# audio.net
KiCad netlist of a schematic drawn in EAGLE
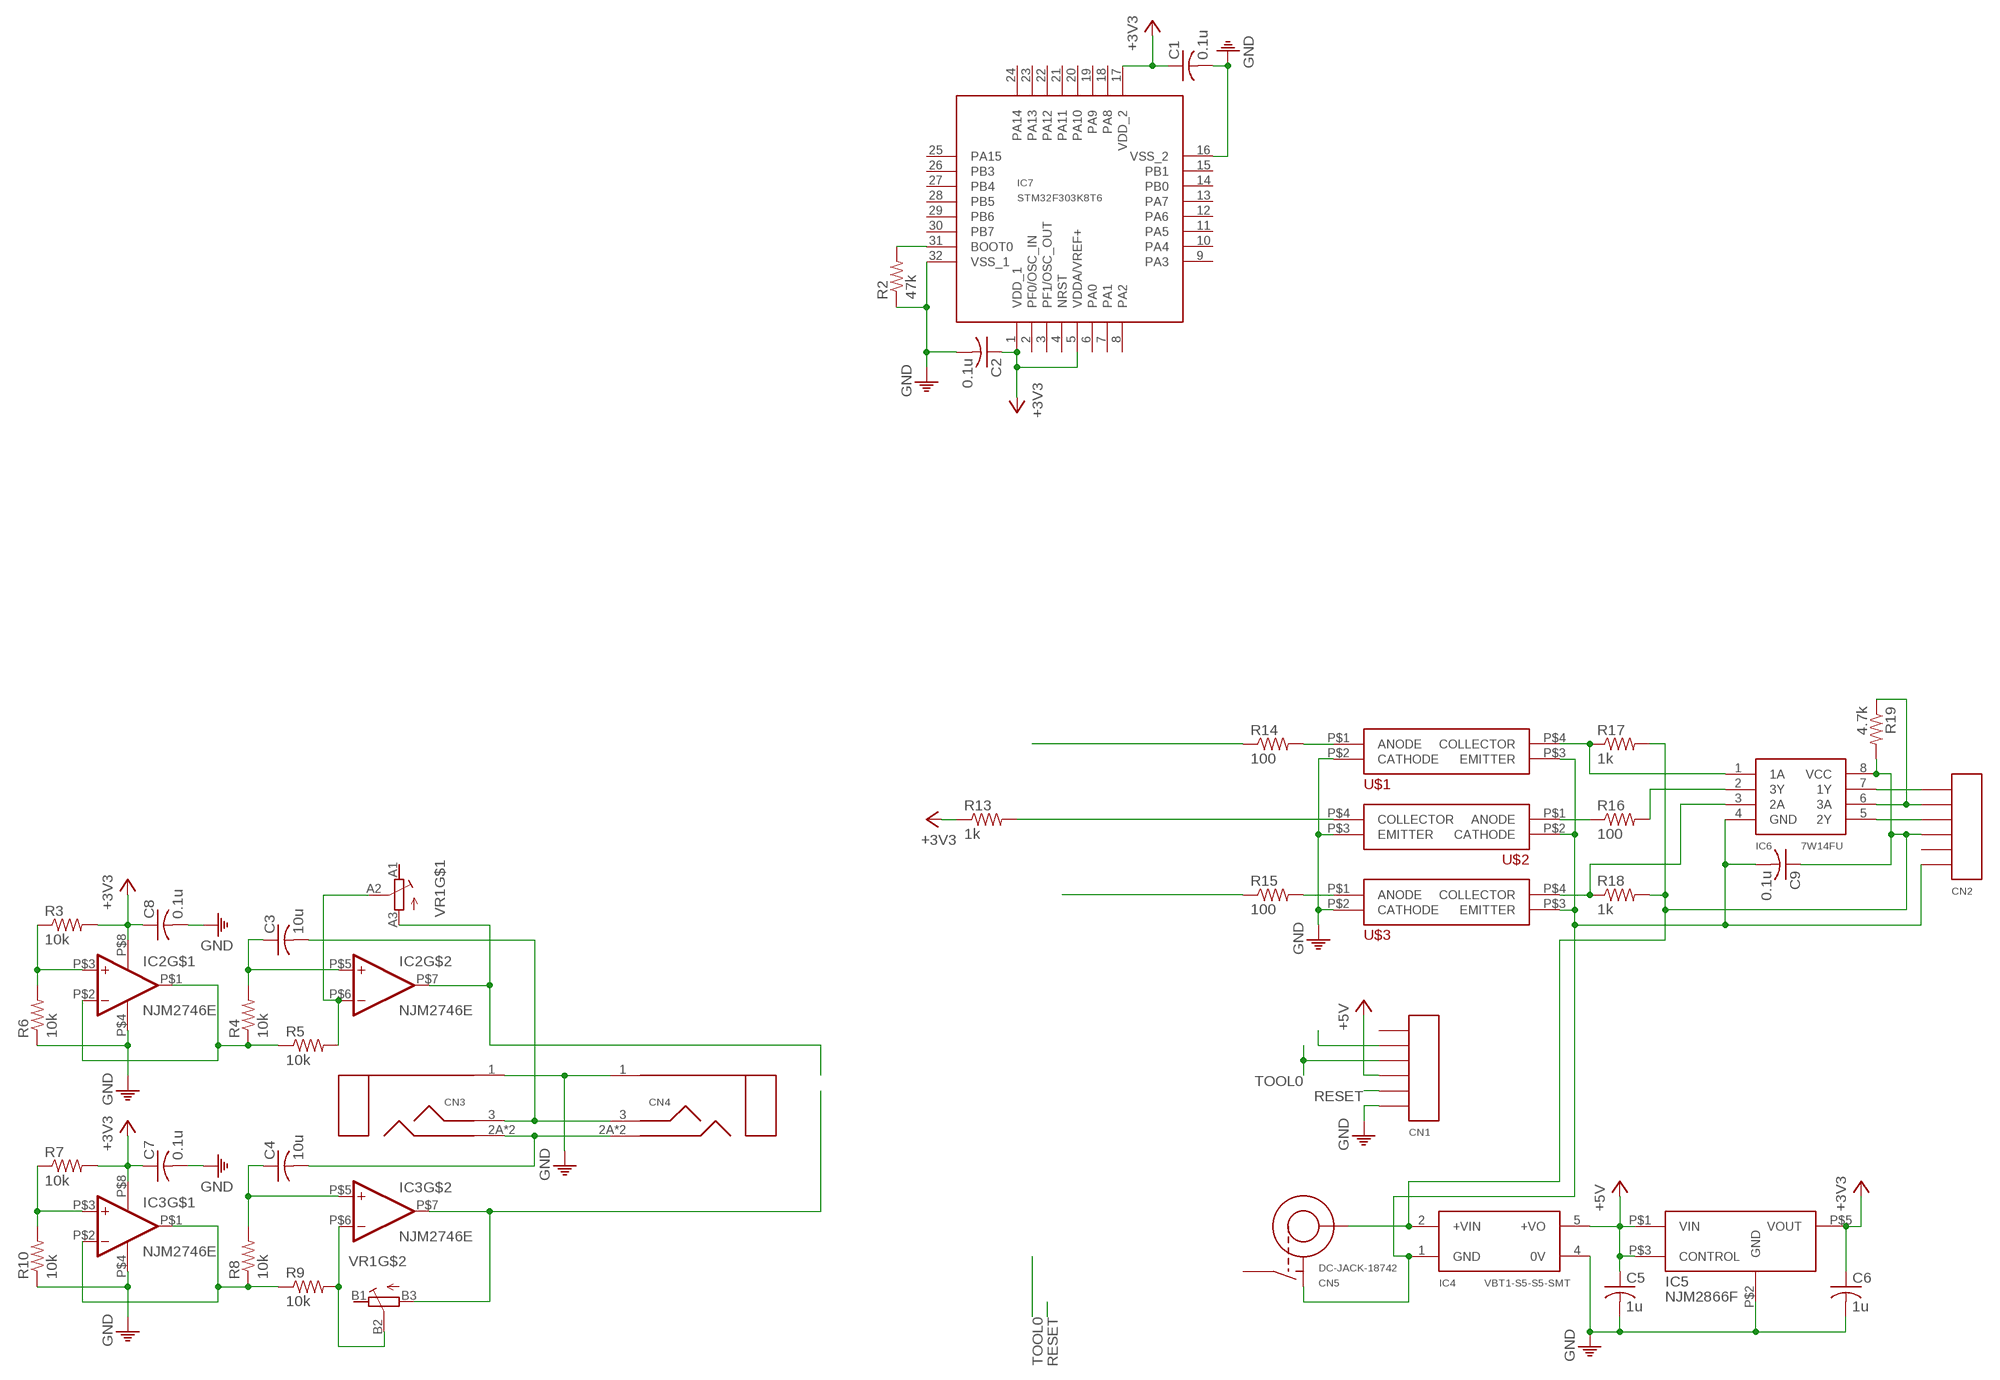
[diagram p0: schematic, sheet 1]

(export (version "E")
  (design (tool "Eeschema 10.0.6"))
  (components
    (comp (ref "C1")
      (value "0.1u")
      (footprint "eagle-import:C2012")
      (libsource (lib "eagle-import") (part "C2012"))
    )
    (comp (ref "C2")
      (value "0.1u")
      (footprint "eagle-import:C2012")
      (libsource (lib "eagle-import") (part "C2012"))
    )
    (comp (ref "C3")
      (value "10u")
      (footprint "eagle-import:C2012")
      (libsource (lib "eagle-import") (part "C2012"))
    )
    (comp (ref "C4")
      (value "10u")
      (footprint "eagle-import:C2012")
      (libsource (lib "eagle-import") (part "C2012"))
    )
    (comp (ref "C5")
      (value "1u")
      (footprint "eagle-import:C2012")
      (libsource (lib "eagle-import") (part "C2012"))
    )
    (comp (ref "C6")
      (value "1u")
      (footprint "eagle-import:C2012")
      (libsource (lib "eagle-import") (part "C2012"))
    )
    (comp (ref "C7")
      (value "0.1u")
      (footprint "eagle-import:C2012")
      (libsource (lib "eagle-import") (part "C2012"))
    )
    (comp (ref "C8")
      (value "0.1u")
      (footprint "eagle-import:C2012")
      (libsource (lib "eagle-import") (part "C2012"))
    )
    (comp (ref "C9")
      (value "0.1u")
      (footprint "eagle-import:C2012")
      (libsource (lib "eagle-import") (part "C2012"))
    )
    (comp (ref "CN1")
      (value "PH-1X06SG")
      (footprint "eagle-import:PH-1X06SG")
      (libsource (lib "eagle-import") (part "PH-1X06SG"))
    )
    (comp (ref "CN2")
      (value "PH-1X06RG")
      (footprint "eagle-import:PH-1X06RG")
      (libsource (lib "eagle-import") (part "PH-1X06RG"))
    )
    (comp (ref "CN3")
      (value "STEREO-3.5-MJ8435")
      (footprint "eagle-import:MJ8435")
      (libsource (lib "eagle-import") (part "STEREO-3.5-MJ8435"))
    )
    (comp (ref "CN4")
      (value "STEREO-3.5-MJ8435")
      (footprint "eagle-import:MJ8435")
      (libsource (lib "eagle-import") (part "STEREO-3.5-MJ8435"))
    )
    (comp (ref "CN5")
      (value "DC-JACK-18742")
      (footprint "eagle-import:18742")
      (libsource (lib "eagle-import") (part "DC-JACK-18742"))
    )
    (comp (ref "IC2")
      (value "NJM2746E")
      (footprint "eagle-import:EMP8")
      (libsource (lib "eagle-import") (part "NJM2746E"))
    )
    (comp (ref "IC3")
      (value "NJM2746E")
      (footprint "eagle-import:EMP8")
      (libsource (lib "eagle-import") (part "NJM2746E"))
    )
    (comp (ref "IC4")
      (value "VBT1-S5-S5-SMT")
      (footprint "eagle-import:VBT1-S5-S5-SMT")
      (libsource (lib "eagle-import") (part "VBT1-S5-S5-SMT"))
    )
    (comp (ref "IC5")
      (value "NJM2866F")
      (footprint "eagle-import:SOT-23-5")
      (libsource (lib "eagle-import") (part "NJM2866F"))
    )
    (comp (ref "IC6")
      (value "7W14FU")
      (footprint "eagle-import:SSOP8-P-0.65")
      (libsource (lib "eagle-import") (part "714FUW"))
    )
    (comp (ref "IC7")
      (value "STM32F303K8T6")
      (footprint "eagle-import:P-LQFP32-7X7-0.80")
      (libsource (lib "eagle-import") (part "STM32F303K8T6"))
    )
    (comp (ref "R2")
      (value "47k")
      (footprint "eagle-import:R2012")
      (libsource (lib "eagle-import") (part "R2012"))
    )
    (comp (ref "R3")
      (value "10k")
      (footprint "eagle-import:R2012")
      (libsource (lib "eagle-import") (part "R2012"))
    )
    (comp (ref "R4")
      (value "10k")
      (footprint "eagle-import:R2012")
      (libsource (lib "eagle-import") (part "R2012"))
    )
    (comp (ref "R5")
      (value "10k")
      (footprint "eagle-import:R2012")
      (libsource (lib "eagle-import") (part "R2012"))
    )
    (comp (ref "R6")
      (value "10k")
      (footprint "eagle-import:R2012")
      (libsource (lib "eagle-import") (part "R2012"))
    )
    (comp (ref "R7")
      (value "10k")
      (footprint "eagle-import:R2012")
      (libsource (lib "eagle-import") (part "R2012"))
    )
    (comp (ref "R8")
      (value "10k")
      (footprint "eagle-import:R2012")
      (libsource (lib "eagle-import") (part "R2012"))
    )
    (comp (ref "R9")
      (value "10k")
      (footprint "eagle-import:R2012")
      (libsource (lib "eagle-import") (part "R2012"))
    )
    (comp (ref "R10")
      (value "10k")
      (footprint "eagle-import:R2012")
      (libsource (lib "eagle-import") (part "R2012"))
    )
    (comp (ref "R13")
      (value "1k")
      (footprint "eagle-import:R2012")
      (libsource (lib "eagle-import") (part "R2012"))
    )
    (comp (ref "R14")
      (value "100")
      (footprint "eagle-import:R2012")
      (libsource (lib "eagle-import") (part "R2012"))
    )
    (comp (ref "R15")
      (value "100")
      (footprint "eagle-import:R2012")
      (libsource (lib "eagle-import") (part "R2012"))
    )
    (comp (ref "R16")
      (value "100")
      (footprint "eagle-import:R2012")
      (libsource (lib "eagle-import") (part "R2012"))
    )
    (comp (ref "R17")
      (value "1k")
      (footprint "eagle-import:R2012")
      (libsource (lib "eagle-import") (part "R2012"))
    )
    (comp (ref "R18")
      (value "1k")
      (footprint "eagle-import:R2012")
      (libsource (lib "eagle-import") (part "R2012"))
    )
    (comp (ref "R19")
      (value "4.7k")
      (footprint "eagle-import:R2012")
      (libsource (lib "eagle-import") (part "R2012"))
    )
    (comp (ref "U$1")
      (value "TLP291")
      (footprint "eagle-import:11-3C1")
      (libsource (lib "eagle-import") (part "TLP291"))
    )
    (comp (ref "U$2")
      (value "TLP291")
      (footprint "eagle-import:11-3C1")
      (libsource (lib "eagle-import") (part "TLP291"))
    )
    (comp (ref "U$3")
      (value "TLP291")
      (footprint "eagle-import:11-3C1")
      (libsource (lib "eagle-import") (part "TLP291"))
    )
    (comp (ref "VR1")
      (value "R-TRIM-RK0971220")
      (footprint "eagle-import:RK0971220-F15-C0-A104")
      (libsource (lib "eagle-import") (part "R-TRIM-RK0971220"))
    )
  )
  (nets
    (net (code "1") (name "+3V3") (class "Default")
      (node (ref "C1") (pin "1") (pinfunction "1_1") (pintype "passive"))
      (node (ref "C2") (pin "1") (pinfunction "1_1") (pintype "passive"))
      (node (ref "C6") (pin "1") (pinfunction "1_1") (pintype "passive"))
      (node (ref "C7") (pin "1") (pinfunction "1_1") (pintype "passive"))
      (node (ref "C8") (pin "1") (pinfunction "1_1") (pintype "passive"))
      (node (ref "IC2") (pin "P$8") (pinfunction "V+_P$8") (pintype "power_in"))
      (node (ref "IC3") (pin "P$8") (pinfunction "V+_P$8") (pintype "power_in"))
      (node (ref "IC5") (pin "P$5") (pinfunction "VOUT_P$5") (pintype "power_in"))
      (node (ref "IC7") (pin "1") (pinfunction "VDD_1_1") (pintype "power_in"))
      (node (ref "IC7") (pin "17") (pinfunction "VDD_2_17") (pintype "power_in"))
      (node (ref "IC7") (pin "5") (pinfunction "VDDA/VREF+_5") (pintype "power_in"))
      (node (ref "R13") (pin "1") (pinfunction "1_1") (pintype "passive"))
      (node (ref "R3") (pin "2") (pinfunction "2_2") (pintype "passive"))
      (node (ref "R7") (pin "2") (pinfunction "2_2") (pintype "passive"))
    )
    (net (code "2") (name "+5V") (class "Default")
      (node (ref "C5") (pin "1") (pinfunction "1_1") (pintype "passive"))
      (node (ref "CN1") (pin "P$4") (pinfunction "P$4_P$4") (pintype "bidirectional"))
      (node (ref "IC4") (pin "5") (pinfunction "+VO_5") (pintype "power_in"))
      (node (ref "IC5") (pin "P$1") (pinfunction "VIN_P$1") (pintype "input"))
      (node (ref "IC5") (pin "P$3") (pinfunction "CONTROL_P$3") (pintype "input"))
    )
    (net (code "3") (name "/RESET") (class "Default")
      (node (ref "CN1") (pin "P$5") (pinfunction "P$5_P$5") (pintype "bidirectional"))
    )
    (net (code "4") (name "/TOOL0") (class "Default")
      (node (ref "CN1") (pin "P$3") (pinfunction "P$3_P$3") (pintype "bidirectional"))
    )
    (net (code "5") (name "GND") (class "Default")
      (node (ref "C1") (pin "2") (pinfunction "2_2") (pintype "passive"))
      (node (ref "C2") (pin "2") (pinfunction "2_2") (pintype "passive"))
      (node (ref "C5") (pin "2") (pinfunction "2_2") (pintype "passive"))
      (node (ref "C6") (pin "2") (pinfunction "2_2") (pintype "passive"))
      (node (ref "C7") (pin "2") (pinfunction "2_2") (pintype "passive"))
      (node (ref "C8") (pin "2") (pinfunction "2_2") (pintype "passive"))
      (node (ref "CN1") (pin "P$6") (pinfunction "P$6_P$6") (pintype "bidirectional"))
      (node (ref "CN3") (pin "1") (pinfunction "SLEEVE_1") (pintype "passive"))
      (node (ref "CN4") (pin "1") (pinfunction "SLEEVE_1") (pintype "passive"))
      (node (ref "IC2") (pin "P$4") (pinfunction "V-_P$4") (pintype "power_in"))
      (node (ref "IC3") (pin "P$4") (pinfunction "V-_P$4") (pintype "power_in"))
      (node (ref "IC4") (pin "4") (pinfunction "0V_4") (pintype "power_in"))
      (node (ref "IC5") (pin "P$2") (pinfunction "GND_P$2") (pintype "power_in"))
      (node (ref "IC7") (pin "16") (pinfunction "VSS_2_16") (pintype "power_in"))
      (node (ref "IC7") (pin "32") (pinfunction "VSS_1_32") (pintype "power_in"))
      (node (ref "R10") (pin "1") (pinfunction "1_1") (pintype "passive"))
      (node (ref "R2") (pin "1") (pinfunction "1_1") (pintype "passive"))
      (node (ref "R6") (pin "1") (pinfunction "1_1") (pintype "passive"))
      (node (ref "U$1") (pin "P$2") (pinfunction "CATHODE_P$2") (pintype "bidirectional"))
      (node (ref "U$2") (pin "P$3") (pinfunction "EMITTER_P$3") (pintype "bidirectional"))
      (node (ref "U$3") (pin "P$2") (pinfunction "CATHODE_P$2") (pintype "bidirectional"))
    )
    (net (code "6") (name "Net-(C4-Pad2)") (class "Default")
      (node (ref "C4") (pin "2") (pinfunction "2_2") (pintype "passive"))
      (node (ref "CN3") (pin "2A") (pinfunction "TIP_2A") (pintype "passive"))
      (node (ref "CN3") (pin "2B") (pinfunction "TIP_2B") (pintype "passive"))
      (node (ref "CN4") (pin "2A") (pinfunction "TIP_2A") (pintype "passive"))
      (node (ref "CN4") (pin "2B") (pinfunction "TIP_2B") (pintype "passive"))
    )
    (net (code "7") (name "Net-(CN3-RING)") (class "Default")
      (node (ref "C3") (pin "2") (pinfunction "2_2") (pintype "passive"))
      (node (ref "CN3") (pin "3") (pinfunction "RING_3") (pintype "passive"))
      (node (ref "CN4") (pin "3") (pinfunction "RING_3") (pintype "passive"))
    )
    (net (code "8") (name "Net-(CN5-CENTER)") (class "Default")
      (node (ref "C9") (pin "1") (pinfunction "1_1") (pintype "passive"))
      (node (ref "CN2") (pin "P$4") (pinfunction "P$4_P$4") (pintype "bidirectional"))
      (node (ref "CN5") (pin "P$1") (pinfunction "CENTER_P$1") (pintype "passive"))
      (node (ref "IC4") (pin "2") (pinfunction "+VIN_2") (pintype "power_in"))
      (node (ref "IC6") (pin "8") (pinfunction "VCC_8") (pintype "power_in"))
      (node (ref "R17") (pin "2") (pinfunction "2_2") (pintype "passive"))
      (node (ref "R18") (pin "2") (pinfunction "2_2") (pintype "passive"))
      (node (ref "R19") (pin "2") (pinfunction "2_2") (pintype "passive"))
    )
    (net (code "9") (name "Net-(CN5-TIP)") (class "Default")
      (node (ref "C9") (pin "2") (pinfunction "2_2") (pintype "passive"))
      (node (ref "CN2") (pin "P$6") (pinfunction "P$6_P$6") (pintype "bidirectional"))
      (node (ref "CN5") (pin "P$2") (pinfunction "TIP_P$2") (pintype "passive"))
      (node (ref "IC4") (pin "1") (pinfunction "GND_1") (pintype "power_in"))
      (node (ref "IC6") (pin "4") (pinfunction "GND_4") (pintype "power_in"))
      (node (ref "U$1") (pin "P$3") (pinfunction "EMITTER_P$3") (pintype "bidirectional"))
      (node (ref "U$2") (pin "P$2") (pinfunction "CATHODE_P$2") (pintype "bidirectional"))
      (node (ref "U$3") (pin "P$3") (pinfunction "EMITTER_P$3") (pintype "bidirectional"))
    )
    (net (code "10") (name "Net-(IC2A-+IN)") (class "Default")
      (node (ref "IC2") (pin "P$3") (pinfunction "+IN_P$3") (pintype "input"))
      (node (ref "R3") (pin "1") (pinfunction "1_1") (pintype "passive"))
      (node (ref "R6") (pin "2") (pinfunction "2_2") (pintype "passive"))
    )
    (net (code "11") (name "Net-(IC2A--IN)") (class "Default")
      (node (ref "IC2") (pin "P$1") (pinfunction "OUT_P$1") (pintype "output"))
      (node (ref "IC2") (pin "P$2") (pinfunction "-IN_P$2") (pintype "input"))
      (node (ref "R4") (pin "1") (pinfunction "1_1") (pintype "passive"))
      (node (ref "R5") (pin "1") (pinfunction "1_1") (pintype "passive"))
    )
    (net (code "12") (name "Net-(IC2B-+IN)") (class "Default")
      (node (ref "C3") (pin "1") (pinfunction "1_1") (pintype "passive"))
      (node (ref "IC2") (pin "P$5") (pinfunction "+IN_P$5") (pintype "input"))
      (node (ref "R4") (pin "2") (pinfunction "2_2") (pintype "passive"))
    )
    (net (code "13") (name "Net-(IC2B--IN)") (class "Default")
      (node (ref "IC2") (pin "P$6") (pinfunction "-IN_P$6") (pintype "input"))
      (node (ref "R5") (pin "2") (pinfunction "2_2") (pintype "passive"))
      (node (ref "VR1") (pin "A2") (pinfunction "S_A2") (pintype "passive"))
    )
    (net (code "14") (name "Net-(IC2B-OUT)") (class "Default")
      (node (ref "IC2") (pin "P$7") (pinfunction "OUT_P$7") (pintype "output"))
      (node (ref "VR1") (pin "A3") (pinfunction "E_A3") (pintype "passive"))
    )
    (net (code "15") (name "Net-(IC3A-+IN)") (class "Default")
      (node (ref "IC3") (pin "P$3") (pinfunction "+IN_P$3") (pintype "input"))
      (node (ref "R10") (pin "2") (pinfunction "2_2") (pintype "passive"))
      (node (ref "R7") (pin "1") (pinfunction "1_1") (pintype "passive"))
    )
    (net (code "16") (name "Net-(IC3A--IN)") (class "Default")
      (node (ref "IC3") (pin "P$1") (pinfunction "OUT_P$1") (pintype "output"))
      (node (ref "IC3") (pin "P$2") (pinfunction "-IN_P$2") (pintype "input"))
      (node (ref "R8") (pin "1") (pinfunction "1_1") (pintype "passive"))
      (node (ref "R9") (pin "1") (pinfunction "1_1") (pintype "passive"))
    )
    (net (code "17") (name "Net-(IC3B-+IN)") (class "Default")
      (node (ref "C4") (pin "1") (pinfunction "1_1") (pintype "passive"))
      (node (ref "IC3") (pin "P$5") (pinfunction "+IN_P$5") (pintype "input"))
      (node (ref "R8") (pin "2") (pinfunction "2_2") (pintype "passive"))
    )
    (net (code "18") (name "Net-(IC3B--IN)") (class "Default")
      (node (ref "IC3") (pin "P$6") (pinfunction "-IN_P$6") (pintype "input"))
      (node (ref "R9") (pin "2") (pinfunction "2_2") (pintype "passive"))
      (node (ref "VR1") (pin "B2") (pinfunction "S_B2") (pintype "passive"))
    )
    (net (code "19") (name "Net-(IC3B-OUT)") (class "Default")
      (node (ref "IC3") (pin "P$7") (pinfunction "OUT_P$7") (pintype "output"))
      (node (ref "VR1") (pin "B3") (pinfunction "E_B3") (pintype "passive"))
    )
    (net (code "20") (name "Net-(IC6-1A)") (class "Default")
      (node (ref "IC6") (pin "1") (pinfunction "1A_1") (pintype "input"))
      (node (ref "R17") (pin "1") (pinfunction "1_1") (pintype "passive"))
      (node (ref "U$1") (pin "P$4") (pinfunction "COLLECTOR_P$4") (pintype "bidirectional"))
    )
    (net (code "21") (name "Net-(IC6-1Y)") (class "Default")
      (node (ref "CN2") (pin "P$1") (pinfunction "P$1_P$1") (pintype "bidirectional"))
      (node (ref "IC6") (pin "7") (pinfunction "1Y_7") (pintype "output"))
    )
    (net (code "22") (name "Net-(IC6-2A)") (class "Default")
      (node (ref "IC6") (pin "3") (pinfunction "2A_3") (pintype "input"))
      (node (ref "R18") (pin "1") (pinfunction "1_1") (pintype "passive"))
      (node (ref "U$3") (pin "P$4") (pinfunction "COLLECTOR_P$4") (pintype "bidirectional"))
    )
    (net (code "23") (name "Net-(IC6-2Y)") (class "Default")
      (node (ref "CN2") (pin "P$3") (pinfunction "P$3_P$3") (pintype "bidirectional"))
      (node (ref "IC6") (pin "5") (pinfunction "2Y_5") (pintype "output"))
    )
    (net (code "24") (name "Net-(IC6-3A)") (class "Default")
      (node (ref "CN2") (pin "P$2") (pinfunction "P$2_P$2") (pintype "bidirectional"))
      (node (ref "IC6") (pin "6") (pinfunction "3A_6") (pintype "input"))
      (node (ref "R19") (pin "1") (pinfunction "1_1") (pintype "passive"))
    )
    (net (code "25") (name "Net-(IC6-3Y)") (class "Default")
      (node (ref "IC6") (pin "2") (pinfunction "3Y_2") (pintype "output"))
      (node (ref "R16") (pin "2") (pinfunction "2_2") (pintype "passive"))
    )
    (net (code "26") (name "Net-(IC7-BOOT0)") (class "Default")
      (node (ref "IC7") (pin "31") (pinfunction "BOOT0_31") (pintype "input"))
      (node (ref "R2") (pin "2") (pinfunction "2_2") (pintype "passive"))
    )
    (net (code "27") (name "Net-(U$1-ANODE)") (class "Default")
      (node (ref "R14") (pin "2") (pinfunction "2_2") (pintype "passive"))
      (node (ref "U$1") (pin "P$1") (pinfunction "ANODE_P$1") (pintype "bidirectional"))
    )
    (net (code "28") (name "Net-(U$2-ANODE)") (class "Default")
      (node (ref "R16") (pin "1") (pinfunction "1_1") (pintype "passive"))
      (node (ref "U$2") (pin "P$1") (pinfunction "ANODE_P$1") (pintype "bidirectional"))
    )
    (net (code "29") (name "Net-(U$2-COLLECTOR)") (class "Default")
      (node (ref "R13") (pin "2") (pinfunction "2_2") (pintype "passive"))
      (node (ref "U$2") (pin "P$4") (pinfunction "COLLECTOR_P$4") (pintype "bidirectional"))
    )
    (net (code "30") (name "Net-(U$3-ANODE)") (class "Default")
      (node (ref "R15") (pin "2") (pinfunction "2_2") (pintype "passive"))
      (node (ref "U$3") (pin "P$1") (pinfunction "ANODE_P$1") (pintype "bidirectional"))
    )
    (net (code "31") (name "unconnected-(CN1-PadP$1)") (class "Default")
      (node (ref "CN1") (pin "P$1") (pinfunction "P$1_P$1") (pintype "bidirectional"))
    )
    (net (code "32") (name "unconnected-(CN1-PadP$2)") (class "Default")
      (node (ref "CN1") (pin "P$2") (pinfunction "P$2_P$2") (pintype "bidirectional"))
    )
    (net (code "33") (name "unconnected-(CN2-PadP$5)") (class "Default")
      (node (ref "CN2") (pin "P$5") (pinfunction "P$5_P$5") (pintype "bidirectional"))
    )
    (net (code "34") (name "unconnected-(CN5-SHUNT-PadP$3)") (class "Default")
      (node (ref "CN5") (pin "P$3") (pinfunction "SHUNT_P$3") (pintype "passive"))
    )
    (net (code "35") (name "unconnected-(IC7-NRST-Pad4)") (class "Default")
      (node (ref "IC7") (pin "4") (pinfunction "NRST_4") (pintype "input"))
    )
    (net (code "36") (name "unconnected-(IC7-PA0-Pad6)") (class "Default")
      (node (ref "IC7") (pin "6") (pinfunction "PA0_6") (pintype "bidirectional"))
    )
    (net (code "37") (name "unconnected-(IC7-PA1-Pad7)") (class "Default")
      (node (ref "IC7") (pin "7") (pinfunction "PA1_7") (pintype "bidirectional"))
    )
    (net (code "38") (name "unconnected-(IC7-PA2-Pad8)") (class "Default")
      (node (ref "IC7") (pin "8") (pinfunction "PA2_8") (pintype "bidirectional"))
    )
    (net (code "39") (name "unconnected-(IC7-PA3-Pad9)") (class "Default")
      (node (ref "IC7") (pin "9") (pinfunction "PA3_9") (pintype "bidirectional"))
    )
    (net (code "40") (name "unconnected-(IC7-PA4-Pad10)") (class "Default")
      (node (ref "IC7") (pin "10") (pinfunction "PA4_10") (pintype "bidirectional"))
    )
    (net (code "41") (name "unconnected-(IC7-PA5-Pad11)") (class "Default")
      (node (ref "IC7") (pin "11") (pinfunction "PA5_11") (pintype "bidirectional"))
    )
    (net (code "42") (name "unconnected-(IC7-PA6-Pad12)") (class "Default")
      (node (ref "IC7") (pin "12") (pinfunction "PA6_12") (pintype "bidirectional"))
    )
    (net (code "43") (name "unconnected-(IC7-PA7-Pad13)") (class "Default")
      (node (ref "IC7") (pin "13") (pinfunction "PA7_13") (pintype "bidirectional"))
    )
    (net (code "44") (name "unconnected-(IC7-PA8-Pad18)") (class "Default")
      (node (ref "IC7") (pin "18") (pinfunction "PA8_18") (pintype "bidirectional"))
    )
    (net (code "45") (name "unconnected-(IC7-PA9-Pad19)") (class "Default")
      (node (ref "IC7") (pin "19") (pinfunction "PA9_19") (pintype "bidirectional"))
    )
    (net (code "46") (name "unconnected-(IC7-PA10-Pad20)") (class "Default")
      (node (ref "IC7") (pin "20") (pinfunction "PA10_20") (pintype "bidirectional"))
    )
    (net (code "47") (name "unconnected-(IC7-PA11-Pad21)") (class "Default")
      (node (ref "IC7") (pin "21") (pinfunction "PA11_21") (pintype "bidirectional"))
    )
    (net (code "48") (name "unconnected-(IC7-PA12-Pad22)") (class "Default")
      (node (ref "IC7") (pin "22") (pinfunction "PA12_22") (pintype "bidirectional"))
    )
    (net (code "49") (name "unconnected-(IC7-PA13-Pad23)") (class "Default")
      (node (ref "IC7") (pin "23") (pinfunction "PA13_23") (pintype "bidirectional"))
    )
    (net (code "50") (name "unconnected-(IC7-PA14-Pad24)") (class "Default")
      (node (ref "IC7") (pin "24") (pinfunction "PA14_24") (pintype "bidirectional"))
    )
    (net (code "51") (name "unconnected-(IC7-PA15-Pad25)") (class "Default")
      (node (ref "IC7") (pin "25") (pinfunction "PA15_25") (pintype "bidirectional"))
    )
    (net (code "52") (name "unconnected-(IC7-PB0-Pad14)") (class "Default")
      (node (ref "IC7") (pin "14") (pinfunction "PB0_14") (pintype "bidirectional"))
    )
    (net (code "53") (name "unconnected-(IC7-PB1-Pad15)") (class "Default")
      (node (ref "IC7") (pin "15") (pinfunction "PB1_15") (pintype "bidirectional"))
    )
    (net (code "54") (name "unconnected-(IC7-PB3-Pad26)") (class "Default")
      (node (ref "IC7") (pin "26") (pinfunction "PB3_26") (pintype "bidirectional"))
    )
    (net (code "55") (name "unconnected-(IC7-PB4-Pad27)") (class "Default")
      (node (ref "IC7") (pin "27") (pinfunction "PB4_27") (pintype "bidirectional"))
    )
    (net (code "56") (name "unconnected-(IC7-PB5-Pad28)") (class "Default")
      (node (ref "IC7") (pin "28") (pinfunction "PB5_28") (pintype "bidirectional"))
    )
    (net (code "57") (name "unconnected-(IC7-PB6-Pad29)") (class "Default")
      (node (ref "IC7") (pin "29") (pinfunction "PB6_29") (pintype "bidirectional"))
    )
    (net (code "58") (name "unconnected-(IC7-PB7-Pad30)") (class "Default")
      (node (ref "IC7") (pin "30") (pinfunction "PB7_30") (pintype "bidirectional"))
    )
    (net (code "59") (name "unconnected-(IC7-PF0{slash}OSC_IN-Pad2)") (class "Default")
      (node (ref "IC7") (pin "2") (pinfunction "PF0/OSC_IN_2") (pintype "bidirectional"))
    )
    (net (code "60") (name "unconnected-(IC7-PF1{slash}OSC_OUT-Pad3)") (class "Default")
      (node (ref "IC7") (pin "3") (pinfunction "PF1/OSC_OUT_3") (pintype "bidirectional"))
    )
    (net (code "61") (name "unconnected-(R14-Pad1)") (class "Default")
      (node (ref "R14") (pin "1") (pinfunction "1_1") (pintype "passive"))
    )
    (net (code "62") (name "unconnected-(R15-Pad1)") (class "Default")
      (node (ref "R15") (pin "1") (pinfunction "1_1") (pintype "passive"))
    )
    (net (code "63") (name "unconnected-(VR1A-A-PadA1)") (class "Default")
      (node (ref "VR1") (pin "A1") (pinfunction "A_A1") (pintype "passive"))
    )
    (net (code "64") (name "unconnected-(VR1B-A-PadB1)") (class "Default")
      (node (ref "VR1") (pin "B1") (pinfunction "A_B1") (pintype "passive"))
    )
  )
)
